# pipower-screw-gndplane.net
KiCad netlist of a schematic drawn in EAGLE
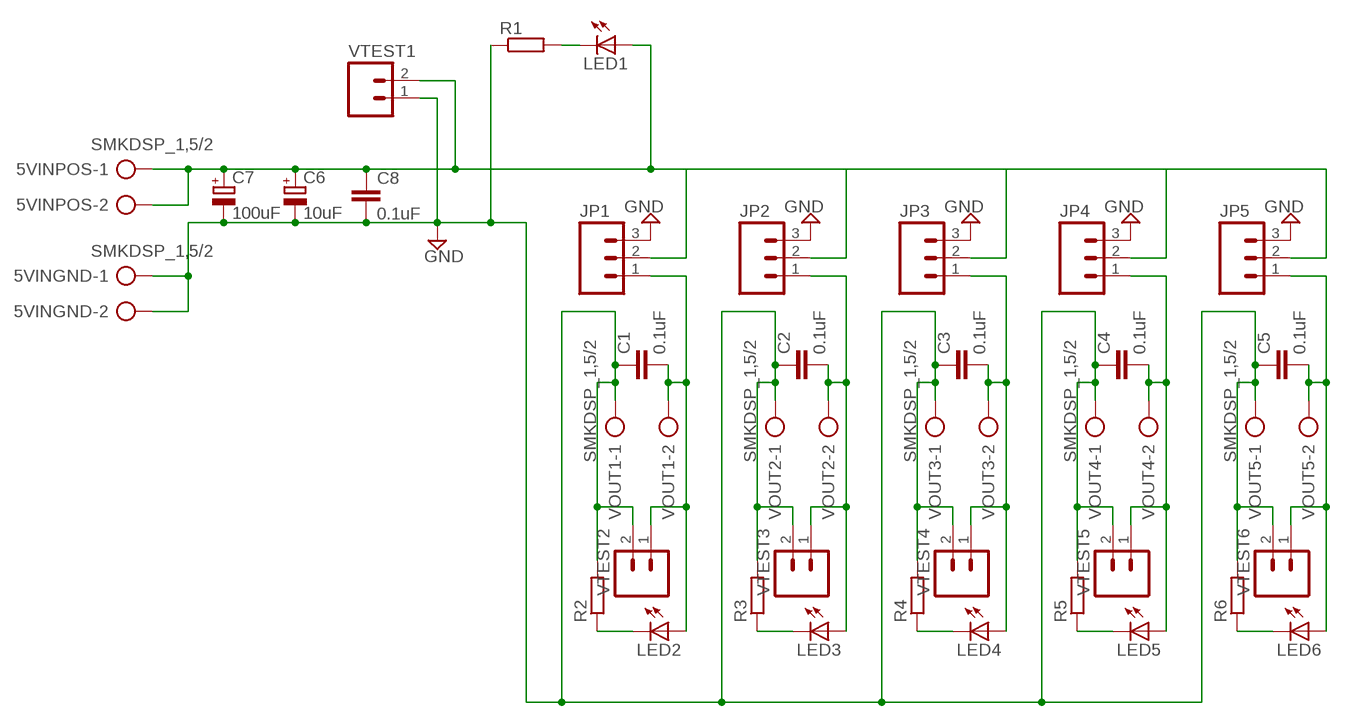
[diagram p0: schematic, sheet 1]

(export (version "E")
  (design (tool "Eeschema 10.0.6"))
  (components
    (comp (ref "5VINGND")
      (value "SMKDSP_1,5/2")
      (footprint "eagle-import:SMKDSP_1,5_2")
      (fields (field (name "MF") "FARNELL") (field (name "MPN") "1733570"))
      (libsource (lib "eagle-import") (part "SMKDSP_1,5/2"))
    )
    (comp (ref "5VINPOS")
      (value "SMKDSP_1,5/2")
      (footprint "eagle-import:SMKDSP_1,5_2")
      (fields (field (name "MF") "FARNELL") (field (name "MPN") "1733570"))
      (libsource (lib "eagle-import") (part "SMKDSP_1,5/2"))
    )
    (comp (ref "C1")
      (value "0.1uF")
      (footprint "eagle-import:CAP-PTH-5MM")
      (libsource (lib "eagle-import") (part "CAPPTH1"))
    )
    (comp (ref "C2")
      (value "0.1uF")
      (footprint "eagle-import:CAP-PTH-5MM")
      (libsource (lib "eagle-import") (part "CAPPTH1"))
    )
    (comp (ref "C3")
      (value "0.1uF")
      (footprint "eagle-import:CAP-PTH-5MM")
      (libsource (lib "eagle-import") (part "CAPPTH1"))
    )
    (comp (ref "C4")
      (value "0.1uF")
      (footprint "eagle-import:CAP-PTH-5MM")
      (libsource (lib "eagle-import") (part "CAPPTH1"))
    )
    (comp (ref "C5")
      (value "0.1uF")
      (footprint "eagle-import:CAP-PTH-5MM")
      (libsource (lib "eagle-import") (part "CAPPTH1"))
    )
    (comp (ref "C6")
      (value "10uF")
      (footprint "eagle-import:E5-10,5")
      (libsource (lib "eagle-import") (part "CPOL-EUE5-10.5"))
    )
    (comp (ref "C7")
      (value "100uF")
      (footprint "eagle-import:E5-10,5")
      (libsource (lib "eagle-import") (part "resistor_CPOL-EUE5-10.5"))
    )
    (comp (ref "C8")
      (value "0.1uF")
      (footprint "eagle-import:CAP-PTH-5MM")
      (libsource (lib "eagle-import") (part "CAPPTH1"))
    )
    (comp (ref "JP1")
      (value "M03LONGPADS")
      (footprint "eagle-import:1X03_LONGPADS")
      (libsource (lib "eagle-import") (part "M03LONGPADS"))
    )
    (comp (ref "JP2")
      (value "M03LONGPADS")
      (footprint "eagle-import:1X03_LONGPADS")
      (libsource (lib "eagle-import") (part "M03LONGPADS"))
    )
    (comp (ref "JP3")
      (value "M03LONGPADS")
      (footprint "eagle-import:1X03_LONGPADS")
      (libsource (lib "eagle-import") (part "M03LONGPADS"))
    )
    (comp (ref "JP4")
      (value "M03LONGPADS")
      (footprint "eagle-import:1X03_LONGPADS")
      (libsource (lib "eagle-import") (part "M03LONGPADS"))
    )
    (comp (ref "JP5")
      (value "M03LONGPADS")
      (footprint "eagle-import:1X03_LONGPADS")
      (libsource (lib "eagle-import") (part "M03LONGPADS"))
    )
    (comp (ref "LED1")
      (value "LED5MM")
      (footprint "eagle-import:LED5MM")
      (libsource (lib "eagle-import") (part "LED5MM"))
    )
    (comp (ref "LED2")
      (value "LED5MM")
      (footprint "eagle-import:LED5MM")
      (libsource (lib "eagle-import") (part "LED5MM"))
    )
    (comp (ref "LED3")
      (value "LED5MM")
      (footprint "eagle-import:LED5MM")
      (libsource (lib "eagle-import") (part "LED5MM"))
    )
    (comp (ref "LED4")
      (value "LED5MM")
      (footprint "eagle-import:LED5MM")
      (libsource (lib "eagle-import") (part "LED5MM"))
    )
    (comp (ref "LED5")
      (value "LED5MM")
      (footprint "eagle-import:LED5MM")
      (libsource (lib "eagle-import") (part "LED5MM"))
    )
    (comp (ref "LED6")
      (value "LED5MM")
      (footprint "eagle-import:LED5MM")
      (libsource (lib "eagle-import") (part "LED5MM"))
    )
    (comp (ref "R1")
      (value "R-EU_0207/12")
      (footprint "eagle-import:0207_12")
      (libsource (lib "eagle-import") (part "R-EU_0207/12"))
    )
    (comp (ref "R2")
      (value "R-EU_0207/12")
      (footprint "eagle-import:0207_12")
      (libsource (lib "eagle-import") (part "R-EU_0207/12"))
    )
    (comp (ref "R3")
      (value "R-EU_0207/12")
      (footprint "eagle-import:0207_12")
      (libsource (lib "eagle-import") (part "R-EU_0207/12"))
    )
    (comp (ref "R4")
      (value "R-EU_0207/12")
      (footprint "eagle-import:0207_12")
      (libsource (lib "eagle-import") (part "R-EU_0207/12"))
    )
    (comp (ref "R5")
      (value "R-EU_0207/12")
      (footprint "eagle-import:0207_12")
      (libsource (lib "eagle-import") (part "R-EU_0207/12"))
    )
    (comp (ref "R6")
      (value "R-EU_0207/12")
      (footprint "eagle-import:0207_12")
      (libsource (lib "eagle-import") (part "R-EU_0207/12"))
    )
    (comp (ref "VOUT1")
      (value "SMKDSP_1,5/2")
      (footprint "eagle-import:SMKDSP_1,5_2")
      (fields (field (name "MF") "FARNELL") (field (name "MPN") "1733570"))
      (libsource (lib "eagle-import") (part "SMKDSP_1,5/2"))
    )
    (comp (ref "VOUT2")
      (value "SMKDSP_1,5/2")
      (footprint "eagle-import:SMKDSP_1,5_2")
      (fields (field (name "MF") "FARNELL") (field (name "MPN") "1733570"))
      (libsource (lib "eagle-import") (part "SMKDSP_1,5/2"))
    )
    (comp (ref "VOUT3")
      (value "SMKDSP_1,5/2")
      (footprint "eagle-import:SMKDSP_1,5_2")
      (fields (field (name "MF") "FARNELL") (field (name "MPN") "1733570"))
      (libsource (lib "eagle-import") (part "SMKDSP_1,5/2"))
    )
    (comp (ref "VOUT4")
      (value "SMKDSP_1,5/2")
      (footprint "eagle-import:SMKDSP_1,5_2")
      (fields (field (name "MF") "FARNELL") (field (name "MPN") "1733570"))
      (libsource (lib "eagle-import") (part "SMKDSP_1,5/2"))
    )
    (comp (ref "VOUT5")
      (value "SMKDSP_1,5/2")
      (footprint "eagle-import:SMKDSP_1,5_2")
      (fields (field (name "MF") "FARNELL") (field (name "MPN") "1733570"))
      (libsource (lib "eagle-import") (part "SMKDSP_1,5/2"))
    )
    (comp (ref "VTEST1")
      (value "M02PTH3")
      (footprint "eagle-import:1X02_LONGPADS")
      (libsource (lib "eagle-import") (part "M02PTH3"))
    )
    (comp (ref "VTEST2")
      (value "M02PTH3")
      (footprint "eagle-import:1X02_LONGPADS")
      (libsource (lib "eagle-import") (part "M02PTH3"))
    )
    (comp (ref "VTEST3")
      (value "M02PTH3")
      (footprint "eagle-import:1X02_LONGPADS")
      (libsource (lib "eagle-import") (part "M02PTH3"))
    )
    (comp (ref "VTEST4")
      (value "M02PTH3")
      (footprint "eagle-import:1X02_LONGPADS")
      (libsource (lib "eagle-import") (part "M02PTH3"))
    )
    (comp (ref "VTEST5")
      (value "M02PTH3")
      (footprint "eagle-import:1X02_LONGPADS")
      (libsource (lib "eagle-import") (part "M02PTH3"))
    )
    (comp (ref "VTEST6")
      (value "M02PTH3")
      (footprint "eagle-import:1X02_LONGPADS")
      (libsource (lib "eagle-import") (part "M02PTH3"))
    )
  )
  (nets
    (net (code "1") (name "GND") (class "Default")
      (node (ref "5VINGND") (pin "1") (pinfunction "KL_1") (pintype "passive"))
      (node (ref "5VINGND") (pin "2") (pinfunction "KL_2") (pintype "passive"))
      (node (ref "C1") (pin "1") (pinfunction "1_1") (pintype "passive"))
      (node (ref "C2") (pin "1") (pinfunction "1_1") (pintype "passive"))
      (node (ref "C3") (pin "1") (pinfunction "1_1") (pintype "passive"))
      (node (ref "C4") (pin "1") (pinfunction "1_1") (pintype "passive"))
      (node (ref "C5") (pin "1") (pinfunction "1_1") (pintype "passive"))
      (node (ref "C6") (pin "-") (pinfunction "-_-") (pintype "passive"))
      (node (ref "C7") (pin "-") (pinfunction "-_-") (pintype "passive"))
      (node (ref "C8") (pin "2") (pinfunction "2_2") (pintype "passive"))
      (node (ref "JP1") (pin "3") (pinfunction "3_3") (pintype "passive"))
      (node (ref "JP2") (pin "3") (pinfunction "3_3") (pintype "passive"))
      (node (ref "JP3") (pin "3") (pinfunction "3_3") (pintype "passive"))
      (node (ref "JP4") (pin "3") (pinfunction "3_3") (pintype "passive"))
      (node (ref "JP5") (pin "3") (pinfunction "3_3") (pintype "passive"))
      (node (ref "R1") (pin "1") (pinfunction "1_1") (pintype "passive"))
      (node (ref "R2") (pin "2") (pinfunction "2_2") (pintype "passive"))
      (node (ref "R3") (pin "2") (pinfunction "2_2") (pintype "passive"))
      (node (ref "R4") (pin "2") (pinfunction "2_2") (pintype "passive"))
      (node (ref "R5") (pin "2") (pinfunction "2_2") (pintype "passive"))
      (node (ref "R6") (pin "2") (pinfunction "2_2") (pintype "passive"))
      (node (ref "VOUT1") (pin "1") (pinfunction "KL_1") (pintype "passive"))
      (node (ref "VOUT2") (pin "1") (pinfunction "KL_1") (pintype "passive"))
      (node (ref "VOUT3") (pin "1") (pinfunction "KL_1") (pintype "passive"))
      (node (ref "VOUT4") (pin "1") (pinfunction "KL_1") (pintype "passive"))
      (node (ref "VOUT5") (pin "1") (pinfunction "KL_1") (pintype "passive"))
      (node (ref "VTEST1") (pin "1") (pinfunction "1_1") (pintype "passive"))
      (node (ref "VTEST2") (pin "2") (pinfunction "2_2") (pintype "passive"))
      (node (ref "VTEST3") (pin "2") (pinfunction "2_2") (pintype "passive"))
      (node (ref "VTEST4") (pin "2") (pinfunction "2_2") (pintype "passive"))
      (node (ref "VTEST5") (pin "2") (pinfunction "2_2") (pintype "passive"))
      (node (ref "VTEST6") (pin "2") (pinfunction "2_2") (pintype "passive"))
    )
    (net (code "2") (name "Net-(5VINPOSA-KL)") (class "Default")
      (node (ref "5VINPOS") (pin "1") (pinfunction "KL_1") (pintype "passive"))
      (node (ref "5VINPOS") (pin "2") (pinfunction "KL_2") (pintype "passive"))
      (node (ref "C6") (pin "+") (pinfunction "+_+") (pintype "passive"))
      (node (ref "C7") (pin "+") (pinfunction "+_+") (pintype "passive"))
      (node (ref "C8") (pin "1") (pinfunction "1_1") (pintype "passive"))
      (node (ref "JP1") (pin "2") (pinfunction "2_2") (pintype "passive"))
      (node (ref "JP2") (pin "2") (pinfunction "2_2") (pintype "passive"))
      (node (ref "JP3") (pin "2") (pinfunction "2_2") (pintype "passive"))
      (node (ref "JP4") (pin "2") (pinfunction "2_2") (pintype "passive"))
      (node (ref "JP5") (pin "2") (pinfunction "2_2") (pintype "passive"))
      (node (ref "LED1") (pin "A") (pinfunction "A_A") (pintype "passive"))
      (node (ref "VTEST1") (pin "2") (pinfunction "2_2") (pintype "passive"))
    )
    (net (code "3") (name "Net-(LED1-C)") (class "Default")
      (node (ref "LED1") (pin "K") (pinfunction "C_K") (pintype "passive"))
      (node (ref "R1") (pin "2") (pinfunction "2_2") (pintype "passive"))
    )
    (net (code "4") (name "Net-(LED2-C)") (class "Default")
      (node (ref "LED2") (pin "K") (pinfunction "C_K") (pintype "passive"))
      (node (ref "R2") (pin "1") (pinfunction "1_1") (pintype "passive"))
    )
    (net (code "5") (name "Net-(LED3-C)") (class "Default")
      (node (ref "LED3") (pin "K") (pinfunction "C_K") (pintype "passive"))
      (node (ref "R3") (pin "1") (pinfunction "1_1") (pintype "passive"))
    )
    (net (code "6") (name "Net-(LED4-C)") (class "Default")
      (node (ref "LED4") (pin "K") (pinfunction "C_K") (pintype "passive"))
      (node (ref "R4") (pin "1") (pinfunction "1_1") (pintype "passive"))
    )
    (net (code "7") (name "Net-(LED5-C)") (class "Default")
      (node (ref "LED5") (pin "K") (pinfunction "C_K") (pintype "passive"))
      (node (ref "R5") (pin "1") (pinfunction "1_1") (pintype "passive"))
    )
    (net (code "8") (name "Net-(LED6-C)") (class "Default")
      (node (ref "LED6") (pin "K") (pinfunction "C_K") (pintype "passive"))
      (node (ref "R6") (pin "1") (pinfunction "1_1") (pintype "passive"))
    )
    (net (code "9") (name "Net-(VOUT1B-KL)") (class "Default")
      (node (ref "C1") (pin "2") (pinfunction "2_2") (pintype "passive"))
      (node (ref "JP1") (pin "1") (pinfunction "1_1") (pintype "passive"))
      (node (ref "LED2") (pin "A") (pinfunction "A_A") (pintype "passive"))
      (node (ref "VOUT1") (pin "2") (pinfunction "KL_2") (pintype "passive"))
      (node (ref "VTEST2") (pin "1") (pinfunction "1_1") (pintype "passive"))
    )
    (net (code "10") (name "Net-(VOUT2B-KL)") (class "Default")
      (node (ref "C2") (pin "2") (pinfunction "2_2") (pintype "passive"))
      (node (ref "JP2") (pin "1") (pinfunction "1_1") (pintype "passive"))
      (node (ref "LED3") (pin "A") (pinfunction "A_A") (pintype "passive"))
      (node (ref "VOUT2") (pin "2") (pinfunction "KL_2") (pintype "passive"))
      (node (ref "VTEST3") (pin "1") (pinfunction "1_1") (pintype "passive"))
    )
    (net (code "11") (name "Net-(VOUT3B-KL)") (class "Default")
      (node (ref "C3") (pin "2") (pinfunction "2_2") (pintype "passive"))
      (node (ref "JP3") (pin "1") (pinfunction "1_1") (pintype "passive"))
      (node (ref "LED4") (pin "A") (pinfunction "A_A") (pintype "passive"))
      (node (ref "VOUT3") (pin "2") (pinfunction "KL_2") (pintype "passive"))
      (node (ref "VTEST4") (pin "1") (pinfunction "1_1") (pintype "passive"))
    )
    (net (code "12") (name "Net-(VOUT4B-KL)") (class "Default")
      (node (ref "C4") (pin "2") (pinfunction "2_2") (pintype "passive"))
      (node (ref "JP4") (pin "1") (pinfunction "1_1") (pintype "passive"))
      (node (ref "LED5") (pin "A") (pinfunction "A_A") (pintype "passive"))
      (node (ref "VOUT4") (pin "2") (pinfunction "KL_2") (pintype "passive"))
      (node (ref "VTEST5") (pin "1") (pinfunction "1_1") (pintype "passive"))
    )
    (net (code "13") (name "Net-(VOUT5B-KL)") (class "Default")
      (node (ref "C5") (pin "2") (pinfunction "2_2") (pintype "passive"))
      (node (ref "JP5") (pin "1") (pinfunction "1_1") (pintype "passive"))
      (node (ref "LED6") (pin "A") (pinfunction "A_A") (pintype "passive"))
      (node (ref "VOUT5") (pin "2") (pinfunction "KL_2") (pintype "passive"))
      (node (ref "VTEST6") (pin "1") (pinfunction "1_1") (pintype "passive"))
    )
  )
)
